# Top.net
KiCad netlist of a schematic drawn in Altium Designer
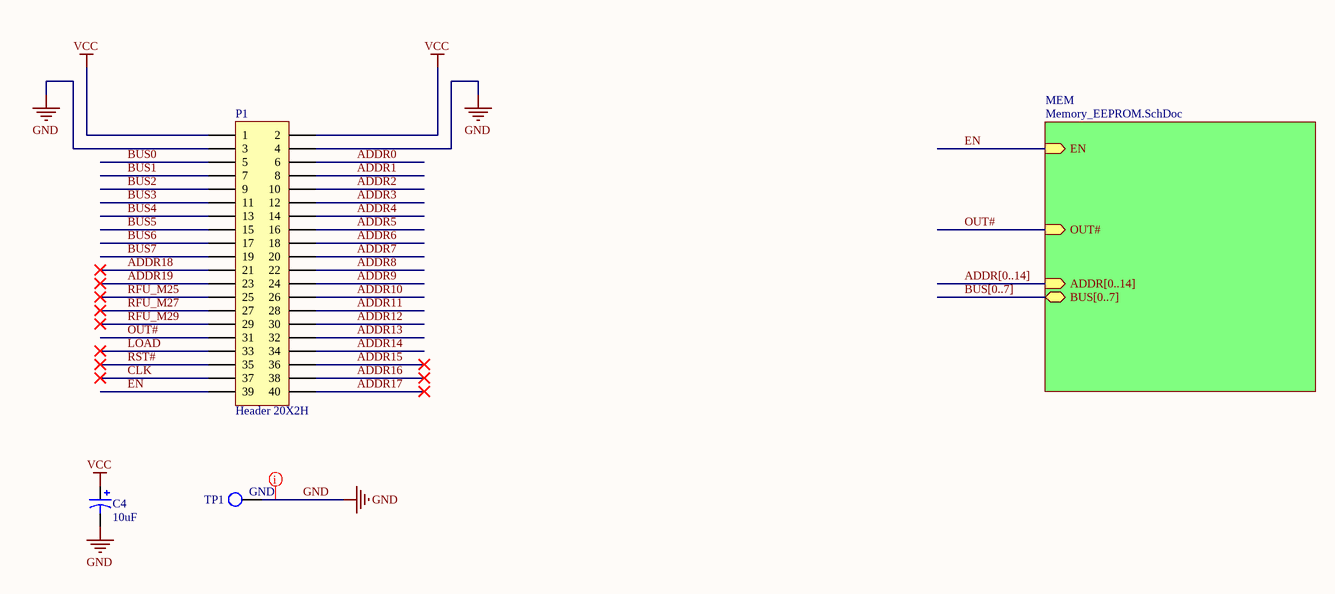
[diagram p0: Top.SchDoc]

(export (version "E")
  (design (tool "Eeschema 10.0.6"))
  (components
    (comp (ref "C4")
      (value "10uF")
      (footprint "C5x7")
      (description "Polarized Capacitor")
      (fields (field (name "Comment") "Cap Pol5") (field (name "PUBLISHER") "Altium Limited"))
      (libsource (lib "Miscellaneous Devices") (part "Cap Pol5"))
    )
    (comp (ref "P1")
      (value "Header 20X2H")
      (footprint "HDR2X20H")
      (description "Header, 20-Pin, Dual row, Right Angle")
      (fields (field (name "PUBLISHER") "Altium Limited"))
      (libsource (lib "Miscellaneous Connectors") (part "Header 20X2H"))
    )
    (comp (ref "TP1") (value "GND") (footprint "KSTN-5011_V") (libsource (lib "TP") (part "TP")))
  )
  (nets
    (net (code "1") (name "/ADDR0") (class "Default")
      (node (ref "P1") (pin "6") (pinfunction "6_6") (pintype "passive"))
    )
    (net (code "2") (name "/ADDR1") (class "Default")
      (node (ref "P1") (pin "8") (pinfunction "8_8") (pintype "passive"))
    )
    (net (code "3") (name "/ADDR2") (class "Default")
      (node (ref "P1") (pin "10") (pinfunction "10_10") (pintype "passive"))
    )
    (net (code "4") (name "/ADDR3") (class "Default")
      (node (ref "P1") (pin "12") (pinfunction "12_12") (pintype "passive"))
    )
    (net (code "5") (name "/ADDR4") (class "Default")
      (node (ref "P1") (pin "14") (pinfunction "14_14") (pintype "passive"))
    )
    (net (code "6") (name "/ADDR5") (class "Default")
      (node (ref "P1") (pin "16") (pinfunction "16_16") (pintype "passive"))
    )
    (net (code "7") (name "/ADDR6") (class "Default")
      (node (ref "P1") (pin "18") (pinfunction "18_18") (pintype "passive"))
    )
    (net (code "8") (name "/ADDR7") (class "Default")
      (node (ref "P1") (pin "20") (pinfunction "20_20") (pintype "passive"))
    )
    (net (code "9") (name "/ADDR8") (class "Default")
      (node (ref "P1") (pin "22") (pinfunction "22_22") (pintype "passive"))
    )
    (net (code "10") (name "/ADDR9") (class "Default")
      (node (ref "P1") (pin "24") (pinfunction "24_24") (pintype "passive"))
    )
    (net (code "11") (name "/ADDR10") (class "Default")
      (node (ref "P1") (pin "26") (pinfunction "26_26") (pintype "passive"))
    )
    (net (code "12") (name "/ADDR11") (class "Default")
      (node (ref "P1") (pin "28") (pinfunction "28_28") (pintype "passive"))
    )
    (net (code "13") (name "/ADDR12") (class "Default")
      (node (ref "P1") (pin "30") (pinfunction "30_30") (pintype "passive"))
    )
    (net (code "14") (name "/ADDR13") (class "Default")
      (node (ref "P1") (pin "32") (pinfunction "32_32") (pintype "passive"))
    )
    (net (code "15") (name "/ADDR14") (class "Default")
      (node (ref "P1") (pin "34") (pinfunction "34_34") (pintype "passive"))
    )
    (net (code "16") (name "/ADDR15") (class "Default")
      (node (ref "P1") (pin "36") (pinfunction "36_36") (pintype "passive+no_connect"))
    )
    (net (code "17") (name "/ADDR16") (class "Default")
      (node (ref "P1") (pin "38") (pinfunction "38_38") (pintype "passive+no_connect"))
    )
    (net (code "18") (name "/ADDR17") (class "Default")
      (node (ref "P1") (pin "40") (pinfunction "40_40") (pintype "passive+no_connect"))
    )
    (net (code "19") (name "/ADDR18") (class "Default")
      (node (ref "P1") (pin "21") (pinfunction "21_21") (pintype "passive+no_connect"))
    )
    (net (code "20") (name "/ADDR19") (class "Default")
      (node (ref "P1") (pin "23") (pinfunction "23_23") (pintype "passive+no_connect"))
    )
    (net (code "22") (name "/BUS0") (class "Default")
      (node (ref "P1") (pin "5") (pinfunction "5_5") (pintype "passive"))
    )
    (net (code "23") (name "/BUS1") (class "Default")
      (node (ref "P1") (pin "7") (pinfunction "7_7") (pintype "passive"))
    )
    (net (code "24") (name "/BUS2") (class "Default")
      (node (ref "P1") (pin "9") (pinfunction "9_9") (pintype "passive"))
    )
    (net (code "25") (name "/BUS3") (class "Default")
      (node (ref "P1") (pin "11") (pinfunction "11_11") (pintype "passive"))
    )
    (net (code "26") (name "/BUS4") (class "Default")
      (node (ref "P1") (pin "13") (pinfunction "13_13") (pintype "passive"))
    )
    (net (code "27") (name "/BUS5") (class "Default")
      (node (ref "P1") (pin "15") (pinfunction "15_15") (pintype "passive"))
    )
    (net (code "28") (name "/BUS6") (class "Default")
      (node (ref "P1") (pin "17") (pinfunction "17_17") (pintype "passive"))
    )
    (net (code "29") (name "/BUS7") (class "Default")
      (node (ref "P1") (pin "19") (pinfunction "19_19") (pintype "passive"))
    )
    (net (code "31") (name "/CLK") (class "Default")
      (node (ref "P1") (pin "37") (pinfunction "37_37") (pintype "passive+no_connect"))
    )
    (net (code "32") (name "/EN") (class "Default")
      (node (ref "P1") (pin "39") (pinfunction "39_39") (pintype "passive"))
    )
    (net (code "33") (name "/LOAD") (class "Default")
      (node (ref "P1") (pin "33") (pinfunction "33_33") (pintype "passive+no_connect"))
    )
    (net (code "34") (name "/OUT#") (class "Default")
      (node (ref "P1") (pin "31") (pinfunction "31_31") (pintype "passive"))
    )
    (net (code "35") (name "/RFU_M25") (class "Default")
      (node (ref "P1") (pin "25") (pinfunction "25_25") (pintype "passive+no_connect"))
    )
    (net (code "36") (name "/RFU_M27") (class "Default")
      (node (ref "P1") (pin "27") (pinfunction "27_27") (pintype "passive+no_connect"))
    )
    (net (code "37") (name "/RFU_M29") (class "Default")
      (node (ref "P1") (pin "29") (pinfunction "29_29") (pintype "passive+no_connect"))
    )
    (net (code "38") (name "/RST#") (class "Default")
      (node (ref "P1") (pin "35") (pinfunction "35_35") (pintype "passive+no_connect"))
    )
    (net (code "39") (name "GND") (class "Default")
      (node (ref "C4") (pin "2") (pinfunction "2_2") (pintype "passive"))
      (node (ref "P1") (pin "3") (pinfunction "3_3") (pintype "passive"))
      (node (ref "P1") (pin "4") (pinfunction "4_4") (pintype "passive"))
      (node (ref "TP1") (pin "1") (pintype "passive"))
    )
    (net (code "40") (name "VCC") (class "Default")
      (node (ref "C4") (pin "1") (pinfunction "1_1") (pintype "passive"))
      (node (ref "P1") (pin "1") (pinfunction "1_1") (pintype "passive"))
      (node (ref "P1") (pin "2") (pinfunction "2_2") (pintype "passive"))
    )
  )
)
